# voltage_measurment.net
KiCad netlist of a schematic drawn in Altium Designer
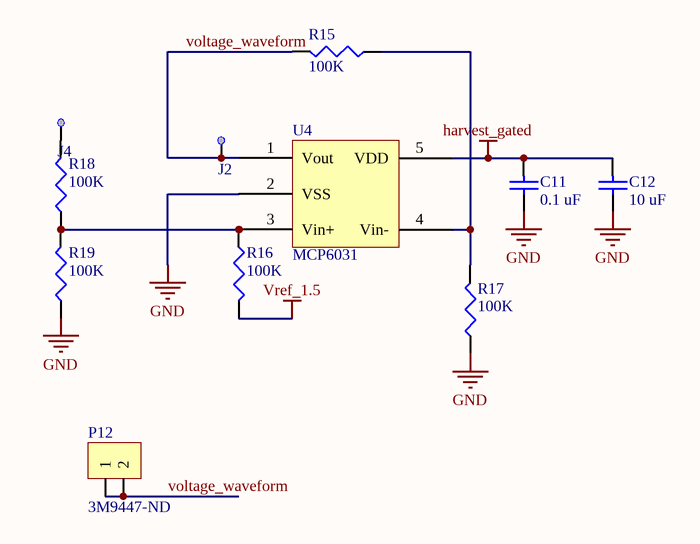
[diagram p0: voltage_measurment.SchDoc]

(export (version "E")
  (design (tool "Eeschema 10.0.6"))
  (components
    (comp (ref "C11")
      (value "0.1 uF")
      (footprint "0603")
      (description "Ceramic capacitor, 0.1 uF, 0603 package")
      (fields (field (name "TOLERANCE") "10%") (field (name "Comment") "Ceramic capacitor"))
      (libsource (lib "rlc") (part "C_0.1u_25V_0603_ceramic"))
    )
    (comp (ref "C12")
      (value "10 uF")
      (footprint "0603")
      (description "Ceramic capacitor, 10 uF, 0603 package")
      (fields (field (name "TOLERANCE") "20%") (field (name "Comment") "Ceramic capacitor"))
      (libsource (lib "rlc") (part "C_10u_6.3V_0603_ceramic"))
    )
    (comp (ref "J2")
      (value "5004")
      (footprint "TestPoint")
      (description "TEST POINT PC MINI .040\"D YELLOW")
      (libsource (lib "connectors") (part "TestPoint"))
    )
    (comp (ref "J4")
      (value "5004")
      (footprint "TestPoint")
      (description "TEST POINT PC MINI .040\"D YELLOW")
      (libsource (lib "connectors") (part "TestPoint"))
    )
    (comp (ref "P12")
      (value "1 x 2 header")
      (footprint "1x2 header")
      (description "100 mils standard header")
      (fields (field (name "SUPPLIER PART NUMBER 1") "3M9447-ND"))
      (libsource (lib "connectors") (part "1 x 2 header"))
    )
    (comp (ref "R15")
      (value "100K")
      (footprint "0603")
      (description "Chip resistor, 100K, 0603 package")
      (fields (field (name "TOLERANCE") "1%") (field (name "POWER") "1/10 W"))
      (libsource (lib "rlc") (part "R_100K_0603"))
    )
    (comp (ref "R16")
      (value "100K")
      (footprint "0603")
      (description "Chip resistor, 100K, 0603 package")
      (fields (field (name "TOLERANCE") "1%") (field (name "POWER") "1/10 W"))
      (libsource (lib "rlc") (part "R_100K_0603"))
    )
    (comp (ref "R17")
      (value "100K")
      (footprint "0603")
      (description "Chip resistor, 100K, 0603 package")
      (fields (field (name "TOLERANCE") "1%") (field (name "POWER") "1/10 W"))
      (libsource (lib "rlc") (part "R_100K_0603"))
    )
    (comp (ref "R18")
      (value "100K")
      (footprint "0603")
      (description "Chip resistor, 100K, 0603 package")
      (fields (field (name "TOLERANCE") "1%") (field (name "POWER") "1/10 W"))
      (libsource (lib "rlc") (part "R_100K_0603"))
    )
    (comp (ref "R19")
      (value "100K")
      (footprint "0603")
      (description "Chip resistor, 100K, 0603 package")
      (fields (field (name "TOLERANCE") "1%") (field (name "POWER") "1/10 W"))
      (libsource (lib "rlc") (part "R_100K_0603"))
    )
    (comp (ref "U4")
      (value "MCP6031")
      (footprint "SOT23-5")
      (description "0.9 µA, High Precision Op Amps")
      (libsource (lib "amplifier") (part "MCP6031"))
    )
  )
  (nets
    (net (code "1") (name "/voltage_waveform") (class "Default")
      (node (ref "J2") (pin "1") (pinfunction "TB_1") (pintype "passive"))
      (node (ref "P12") (pin "1") (pinfunction "1_1") (pintype "passive"))
      (node (ref "P12") (pin "2") (pinfunction "2_2") (pintype "passive"))
      (node (ref "R15") (pin "1") (pintype "passive"))
      (node (ref "U4") (pin "1") (pinfunction "Vout_1") (pintype "passive"))
    )
    (net (code "2") (name "GND") (class "Default")
      (node (ref "C11") (pin "2") (pintype "passive"))
      (node (ref "C12") (pin "2") (pintype "passive"))
      (node (ref "R17") (pin "2") (pintype "passive"))
      (node (ref "R19") (pin "2") (pintype "passive"))
      (node (ref "U4") (pin "2") (pinfunction "VSS_2") (pintype "passive"))
    )
    (net (code "3") (name "Net-(J4-TB)") (class "Default")
      (node (ref "J4") (pin "1") (pinfunction "TB_1") (pintype "passive"))
      (node (ref "R18") (pin "1") (pintype "passive"))
    )
    (net (code "4") (name "Net-(U4-Vin+)") (class "Default")
      (node (ref "R16") (pin "2") (pintype "passive"))
      (node (ref "R18") (pin "2") (pintype "passive"))
      (node (ref "R19") (pin "1") (pintype "passive"))
      (node (ref "U4") (pin "3") (pinfunction "Vin+_3") (pintype "passive"))
    )
    (net (code "5") (name "Net-(U4-Vin-)") (class "Default")
      (node (ref "R15") (pin "2") (pintype "passive"))
      (node (ref "R17") (pin "1") (pintype "passive"))
      (node (ref "U4") (pin "4") (pinfunction "Vin-_4") (pintype "passive"))
    )
    (net (code "6") (name "Vref_1.5") (class "Default") (node (ref "R16") (pin "1") (pintype "passive")))
    (net (code "7") (name "harvest_gated") (class "Default")
      (node (ref "C11") (pin "1") (pintype "passive"))
      (node (ref "C12") (pin "1") (pintype "passive"))
      (node (ref "U4") (pin "5") (pinfunction "VDD_5") (pintype "passive"))
    )
  )
)
